# m1k-input-divider.net
KiCad netlist of a schematic drawn in EAGLE
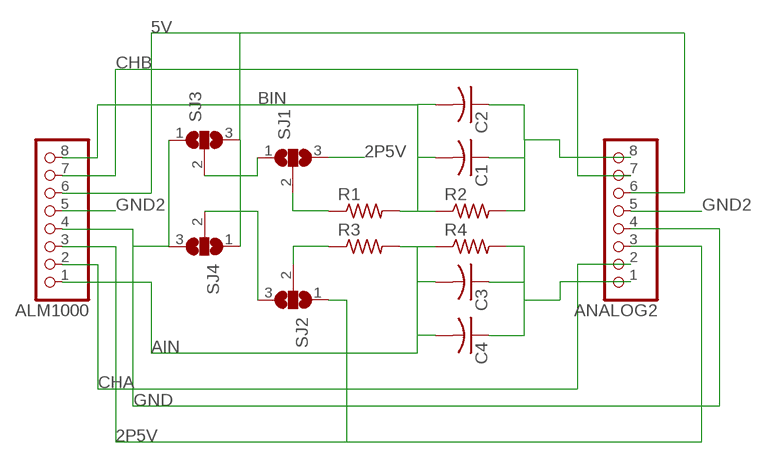
[diagram p0: schematic, sheet 1]

(export (version "E")
  (design (tool "Eeschema 10.0.6"))
  (components
    (comp (ref "ALM1000")
      (value "PINHD-1X8")
      (footprint "eagle-import:1X08")
      (libsource (lib "eagle-import") (part "PINHD-1X8"))
    )
    (comp (ref "ANALOG2")
      (value "PINHD-1X8")
      (footprint "eagle-import:1X08")
      (libsource (lib "eagle-import") (part "PINHD-1X8"))
    )
    (comp (ref "C1")
      (value "C-US050-024X044")
      (footprint "eagle-import:C050-024X044")
      (libsource (lib "eagle-import") (part "C-US050-024X044"))
    )
    (comp (ref "C2")
      (value "C-US050-024X044")
      (footprint "eagle-import:C050-024X044")
      (libsource (lib "eagle-import") (part "C-US050-024X044"))
    )
    (comp (ref "C3")
      (value "C-US050-024X044")
      (footprint "eagle-import:C050-024X044")
      (libsource (lib "eagle-import") (part "C-US050-024X044"))
    )
    (comp (ref "C4")
      (value "C-US050-024X044")
      (footprint "eagle-import:C050-024X044")
      (libsource (lib "eagle-import") (part "C-US050-024X044"))
    )
    (comp (ref "R1")
      (value "R-US_0204/7")
      (footprint "eagle-import:0204_7")
      (libsource (lib "eagle-import") (part "R-US_0204/7"))
    )
    (comp (ref "R2")
      (value "R-US_0204/7")
      (footprint "eagle-import:0204_7")
      (libsource (lib "eagle-import") (part "R-US_0204/7"))
    )
    (comp (ref "R3")
      (value "R-US_0204/7")
      (footprint "eagle-import:0204_7")
      (libsource (lib "eagle-import") (part "R-US_0204/7"))
    )
    (comp (ref "R4")
      (value "R-US_0204/7")
      (footprint "eagle-import:0204_7")
      (libsource (lib "eagle-import") (part "R-US_0204/7"))
    )
    (comp (ref "SJ1")
      (value "SJ2W")
      (footprint "eagle-import:SJ_2")
      (libsource (lib "eagle-import") (part "SJ2W"))
    )
    (comp (ref "SJ2")
      (value "SJ2W")
      (footprint "eagle-import:SJ_2")
      (libsource (lib "eagle-import") (part "SJ2W"))
    )
    (comp (ref "SJ3")
      (value "SJ2W")
      (footprint "eagle-import:SJ_2")
      (libsource (lib "eagle-import") (part "SJ2W"))
    )
    (comp (ref "SJ4")
      (value "SJ2W")
      (footprint "eagle-import:SJ_2")
      (libsource (lib "eagle-import") (part "SJ2W"))
    )
  )
  (nets
    (net (code "1") (name "/2P5V") (class "Default")
      (node (ref "ALM1000") (pin "3") (pinfunction "3_3") (pintype "passive"))
      (node (ref "ANALOG2") (pin "3") (pinfunction "3_3") (pintype "passive"))
      (node (ref "SJ1") (pin "3") (pinfunction "3_3") (pintype "passive"))
      (node (ref "SJ2") (pin "1") (pinfunction "1_1") (pintype "passive"))
    )
    (net (code "2") (name "/5V") (class "Default")
      (node (ref "ALM1000") (pin "6") (pinfunction "6_6") (pintype "passive"))
      (node (ref "ANALOG2") (pin "6") (pinfunction "6_6") (pintype "passive"))
      (node (ref "SJ3") (pin "3") (pinfunction "3_3") (pintype "passive"))
      (node (ref "SJ4") (pin "1") (pinfunction "1_1") (pintype "passive"))
    )
    (net (code "3") (name "/AIN") (class "Default")
      (node (ref "ALM1000") (pin "1") (pinfunction "1_1") (pintype "passive"))
      (node (ref "C3") (pin "2") (pinfunction "2_2") (pintype "passive"))
      (node (ref "C4") (pin "2") (pinfunction "2_2") (pintype "passive"))
      (node (ref "R3") (pin "2") (pinfunction "2_2") (pintype "passive"))
      (node (ref "R4") (pin "1") (pinfunction "1_1") (pintype "passive"))
    )
    (net (code "4") (name "/BIN") (class "Default")
      (node (ref "ALM1000") (pin "8") (pinfunction "8_8") (pintype "passive"))
      (node (ref "C1") (pin "2") (pinfunction "2_2") (pintype "passive"))
      (node (ref "C2") (pin "2") (pinfunction "2_2") (pintype "passive"))
      (node (ref "R1") (pin "2") (pinfunction "2_2") (pintype "passive"))
      (node (ref "R2") (pin "1") (pinfunction "1_1") (pintype "passive"))
    )
    (net (code "5") (name "/CHA") (class "Default")
      (node (ref "ALM1000") (pin "2") (pinfunction "2_2") (pintype "passive"))
      (node (ref "ANALOG2") (pin "2") (pinfunction "2_2") (pintype "passive"))
    )
    (net (code "6") (name "/CHB") (class "Default")
      (node (ref "ALM1000") (pin "7") (pinfunction "7_7") (pintype "passive"))
      (node (ref "ANALOG2") (pin "7") (pinfunction "7_7") (pintype "passive"))
    )
    (net (code "7") (name "/GND") (class "Default")
      (node (ref "ALM1000") (pin "4") (pinfunction "4_4") (pintype "passive"))
      (node (ref "ANALOG2") (pin "4") (pinfunction "4_4") (pintype "passive"))
      (node (ref "SJ3") (pin "1") (pinfunction "1_1") (pintype "passive"))
      (node (ref "SJ4") (pin "3") (pinfunction "3_3") (pintype "passive"))
    )
    (net (code "8") (name "/GND2") (class "Default")
      (node (ref "ALM1000") (pin "5") (pinfunction "5_5") (pintype "passive"))
      (node (ref "ANALOG2") (pin "5") (pinfunction "5_5") (pintype "passive"))
    )
    (net (code "9") (name "Net-(ANALOG2-Pad1)") (class "Default")
      (node (ref "ANALOG2") (pin "1") (pinfunction "1_1") (pintype "passive"))
      (node (ref "C3") (pin "1") (pinfunction "1_1") (pintype "passive"))
      (node (ref "C4") (pin "1") (pinfunction "1_1") (pintype "passive"))
      (node (ref "R4") (pin "2") (pinfunction "2_2") (pintype "passive"))
    )
    (net (code "10") (name "Net-(ANALOG2-Pad8)") (class "Default")
      (node (ref "ANALOG2") (pin "8") (pinfunction "8_8") (pintype "passive"))
      (node (ref "C1") (pin "1") (pinfunction "1_1") (pintype "passive"))
      (node (ref "C2") (pin "1") (pinfunction "1_1") (pintype "passive"))
      (node (ref "R2") (pin "2") (pinfunction "2_2") (pintype "passive"))
    )
    (net (code "11") (name "Net-(R1-Pad1)") (class "Default")
      (node (ref "R1") (pin "1") (pinfunction "1_1") (pintype "passive"))
      (node (ref "SJ1") (pin "2") (pinfunction "2_2") (pintype "passive"))
    )
    (net (code "12") (name "Net-(R3-Pad1)") (class "Default")
      (node (ref "R3") (pin "1") (pinfunction "1_1") (pintype "passive"))
      (node (ref "SJ2") (pin "2") (pinfunction "2_2") (pintype "passive"))
    )
    (net (code "13") (name "Net-(SJ1-Pad1)") (class "Default")
      (node (ref "SJ1") (pin "1") (pinfunction "1_1") (pintype "passive"))
      (node (ref "SJ3") (pin "2") (pinfunction "2_2") (pintype "passive"))
    )
    (net (code "14") (name "Net-(SJ2-Pad3)") (class "Default")
      (node (ref "SJ2") (pin "3") (pinfunction "3_3") (pintype "passive"))
      (node (ref "SJ4") (pin "2") (pinfunction "2_2") (pintype "passive"))
    )
  )
)
